# medusa-ai-sensors.net
KiCad netlist of a schematic drawn in Altium Designer
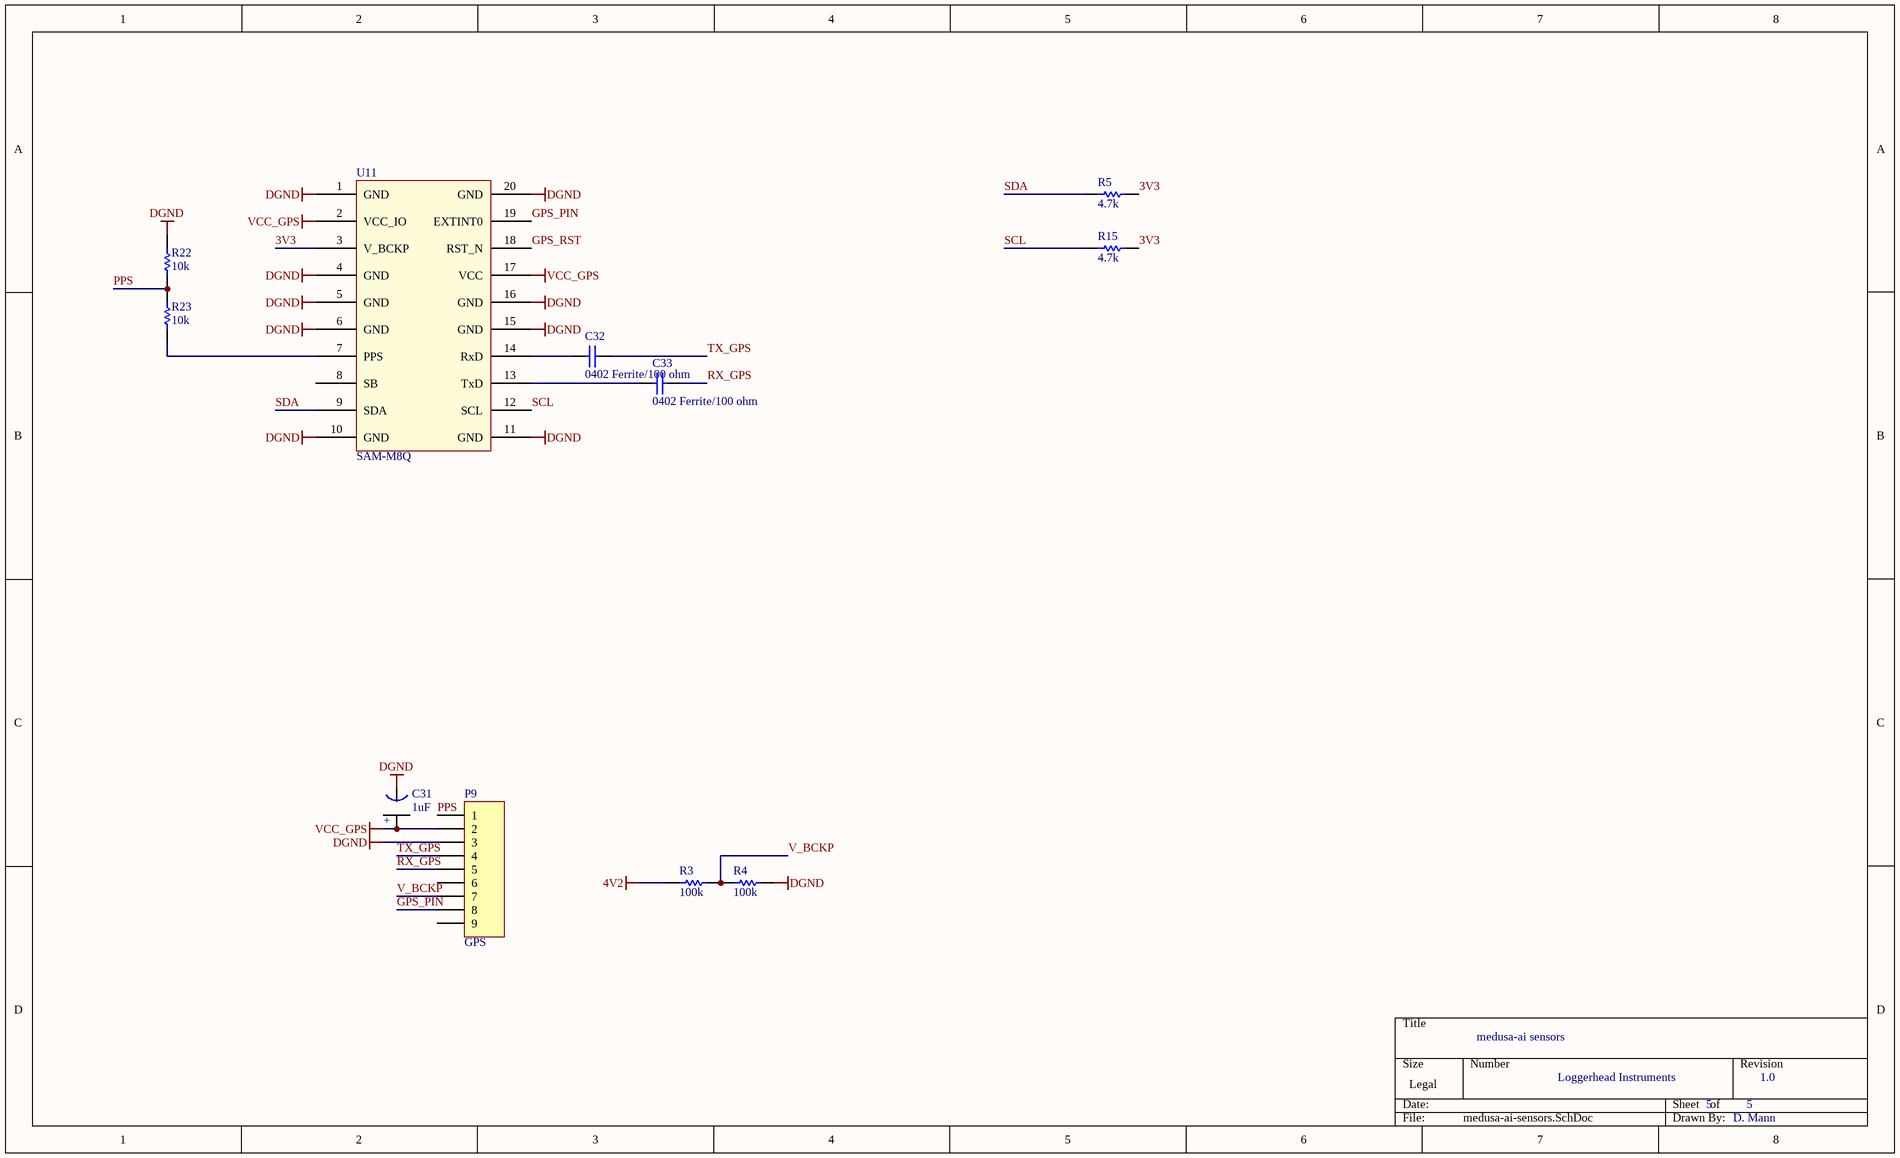
[diagram p0: medusa-ai-sensors.SchDoc]

(export (version "E")
  (design (tool "Eeschema 10.0.6"))
  (components
    (comp (ref "C31") (value "1uF") (footprint "Tant0805") (libsource (lib "Loggerhead") (part "Tant0805")))
    (comp (ref "C32")
      (value "0402 Ferrite/100 ohm")
      (footprint "0402")
      (description "Ceramic Chip Capacitor - Standard")
      (fields (field (name "PUBLISHER") "Altium Limited"))
      (libsource (lib "KEMET Chip Capacitor") (part "C0402"))
    )
    (comp (ref "C33")
      (value "0402 Ferrite/100 ohm")
      (footprint "0402")
      (description "Ceramic Chip Capacitor - Standard")
      (fields (field (name "PUBLISHER") "Altium Limited"))
      (libsource (lib "KEMET Chip Capacitor") (part "C0402"))
    )
    (comp (ref "P9")
      (value "GPS")
      (footprint "HDR1X9")
      (description "Header, 9-Pin")
      (fields (field (name "PUBLISHER") "Altium Limited"))
      (libsource (lib "Miscellaneous Connectors") (part "Header 9"))
    )
    (comp (ref "R3")
      (value "100k")
      (footprint "3-0603")
      (fields (field (name "PUBLISHER") "Altium Limited"))
      (libsource (lib "Panasonic Resistor") (part "ERJ3RK"))
    )
    (comp (ref "R4")
      (value "100k")
      (footprint "3-0603")
      (fields (field (name "PUBLISHER") "Altium Limited"))
      (libsource (lib "Panasonic Resistor") (part "ERJ3RK"))
    )
    (comp (ref "R5")
      (value "4.7k")
      (footprint "3-0603")
      (fields (field (name "PUBLISHER") "Altium Limited"))
      (libsource (lib "Panasonic Resistor") (part "ERJ3RK"))
    )
    (comp (ref "R15")
      (value "4.7k")
      (footprint "3-0603")
      (fields (field (name "PUBLISHER") "Altium Limited"))
      (libsource (lib "Panasonic Resistor") (part "ERJ3RK"))
    )
    (comp (ref "R22")
      (value "10k")
      (footprint "3-0603")
      (fields (field (name "PUBLISHER") "Altium Limited"))
      (libsource (lib "Panasonic Resistor") (part "ERJ3RK"))
    )
    (comp (ref "R23")
      (value "10k")
      (footprint "3-0603")
      (fields (field (name "PUBLISHER") "Altium Limited"))
      (libsource (lib "Panasonic Resistor") (part "ERJ3RK"))
    )
    (comp (ref "U11")
      (value "SAM-M8Q")
      (footprint "GPS SAM-MQ8")
      (libsource (lib "Loggerhead") (part "GPS SAM-M8Q"))
    )
  )
  (nets
    (net (code "1") (name "/3V3") (class "Default")
      (node (ref "R15") (pin "2") (pinfunction "2_2") (pintype "passive"))
      (node (ref "R5") (pin "2") (pinfunction "2_2") (pintype "passive"))
      (node (ref "U11") (pin "3") (pinfunction "V_BCKP_3") (pintype "passive"))
    )
    (net (code "2") (name "/GPS_PIN") (class "Default")
      (node (ref "P9") (pin "8") (pinfunction "8_8") (pintype "passive"))
      (node (ref "U11") (pin "19") (pinfunction "EXTINT0_19") (pintype "passive"))
    )
    (net (code "3") (name "/GPS_RST") (class "Default")
      (node (ref "U11") (pin "18") (pinfunction "RST_N_18") (pintype "passive"))
    )
    (net (code "4") (name "/PPS") (class "Default")
      (node (ref "P9") (pin "1") (pinfunction "1_1") (pintype "passive"))
      (node (ref "R22") (pin "2") (pinfunction "2_2") (pintype "passive"))
      (node (ref "R23") (pin "1") (pinfunction "1_1") (pintype "passive"))
    )
    (net (code "5") (name "/RX_GPS") (class "Default")
      (node (ref "C33") (pin "2") (pinfunction "2_2") (pintype "passive"))
      (node (ref "P9") (pin "5") (pinfunction "5_5") (pintype "passive"))
    )
    (net (code "6") (name "/SCL") (class "Default")
      (node (ref "R15") (pin "1") (pinfunction "1_1") (pintype "passive"))
      (node (ref "U11") (pin "12") (pinfunction "SCL_12") (pintype "passive"))
    )
    (net (code "7") (name "/SDA") (class "Default")
      (node (ref "R5") (pin "1") (pinfunction "1_1") (pintype "passive"))
      (node (ref "U11") (pin "9") (pinfunction "SDA_9") (pintype "passive"))
    )
    (net (code "8") (name "/TX_GPS") (class "Default")
      (node (ref "C32") (pin "2") (pinfunction "2_2") (pintype "passive"))
      (node (ref "P9") (pin "4") (pinfunction "4_4") (pintype "passive"))
    )
    (net (code "9") (name "/V_BCKP") (class "Default")
      (node (ref "P9") (pin "7") (pinfunction "7_7") (pintype "passive"))
      (node (ref "R3") (pin "1") (pinfunction "1_1") (pintype "passive"))
      (node (ref "R4") (pin "2") (pinfunction "2_2") (pintype "passive"))
    )
    (net (code "10") (name "4V2") (class "Default")
      (node (ref "R3") (pin "2") (pinfunction "2_2") (pintype "passive"))
    )
    (net (code "11") (name "DGND") (class "Default")
      (node (ref "C31") (pin "1") (pinfunction "GND_1") (pintype "passive"))
      (node (ref "P9") (pin "3") (pinfunction "3_3") (pintype "passive"))
      (node (ref "R22") (pin "1") (pinfunction "1_1") (pintype "passive"))
      (node (ref "R4") (pin "1") (pinfunction "1_1") (pintype "passive"))
      (node (ref "U11") (pin "1") (pinfunction "GND_1") (pintype "passive"))
      (node (ref "U11") (pin "10") (pinfunction "GND_10") (pintype "passive"))
      (node (ref "U11") (pin "11") (pinfunction "GND_11") (pintype "passive"))
      (node (ref "U11") (pin "15") (pinfunction "GND_15") (pintype "passive"))
      (node (ref "U11") (pin "16") (pinfunction "GND_16") (pintype "passive"))
      (node (ref "U11") (pin "20") (pinfunction "GND_20") (pintype "passive"))
      (node (ref "U11") (pin "4") (pinfunction "GND_4") (pintype "passive"))
      (node (ref "U11") (pin "5") (pinfunction "GND_5") (pintype "passive"))
      (node (ref "U11") (pin "6") (pinfunction "GND_6") (pintype "passive"))
    )
    (net (code "12") (name "Net-(U11-PPS)") (class "Default")
      (node (ref "R23") (pin "2") (pinfunction "2_2") (pintype "passive"))
      (node (ref "U11") (pin "7") (pinfunction "PPS_7") (pintype "passive"))
    )
    (net (code "13") (name "Net-(U11-RxD)") (class "Default")
      (node (ref "C32") (pin "1") (pinfunction "1_1") (pintype "passive"))
      (node (ref "U11") (pin "14") (pinfunction "RxD_14") (pintype "passive"))
    )
    (net (code "14") (name "Net-(U11-TxD)") (class "Default")
      (node (ref "C33") (pin "1") (pinfunction "1_1") (pintype "passive"))
      (node (ref "U11") (pin "13") (pinfunction "TxD_13") (pintype "passive"))
    )
    (net (code "15") (name "VCC_GPS") (class "Default")
      (node (ref "C31") (pin "2") (pinfunction "+_2") (pintype "passive"))
      (node (ref "P9") (pin "2") (pinfunction "2_2") (pintype "passive"))
      (node (ref "U11") (pin "17") (pinfunction "VCC_17") (pintype "passive"))
      (node (ref "U11") (pin "2") (pinfunction "VCC_IO_2") (pintype "passive"))
    )
    (net (code "16") (name "unconnected-(P9-Pad6)") (class "Default")
      (node (ref "P9") (pin "6") (pinfunction "6_6") (pintype "passive"))
    )
    (net (code "17") (name "unconnected-(P9-Pad9)") (class "Default")
      (node (ref "P9") (pin "9") (pinfunction "9_9") (pintype "passive"))
    )
    (net (code "18") (name "unconnected-(U11-SB-Pad8)") (class "Default")
      (node (ref "U11") (pin "8") (pinfunction "SB_8") (pintype "passive"))
    )
  )
)
